# main.net
KiCad netlist of a schematic drawn in Altium Designer
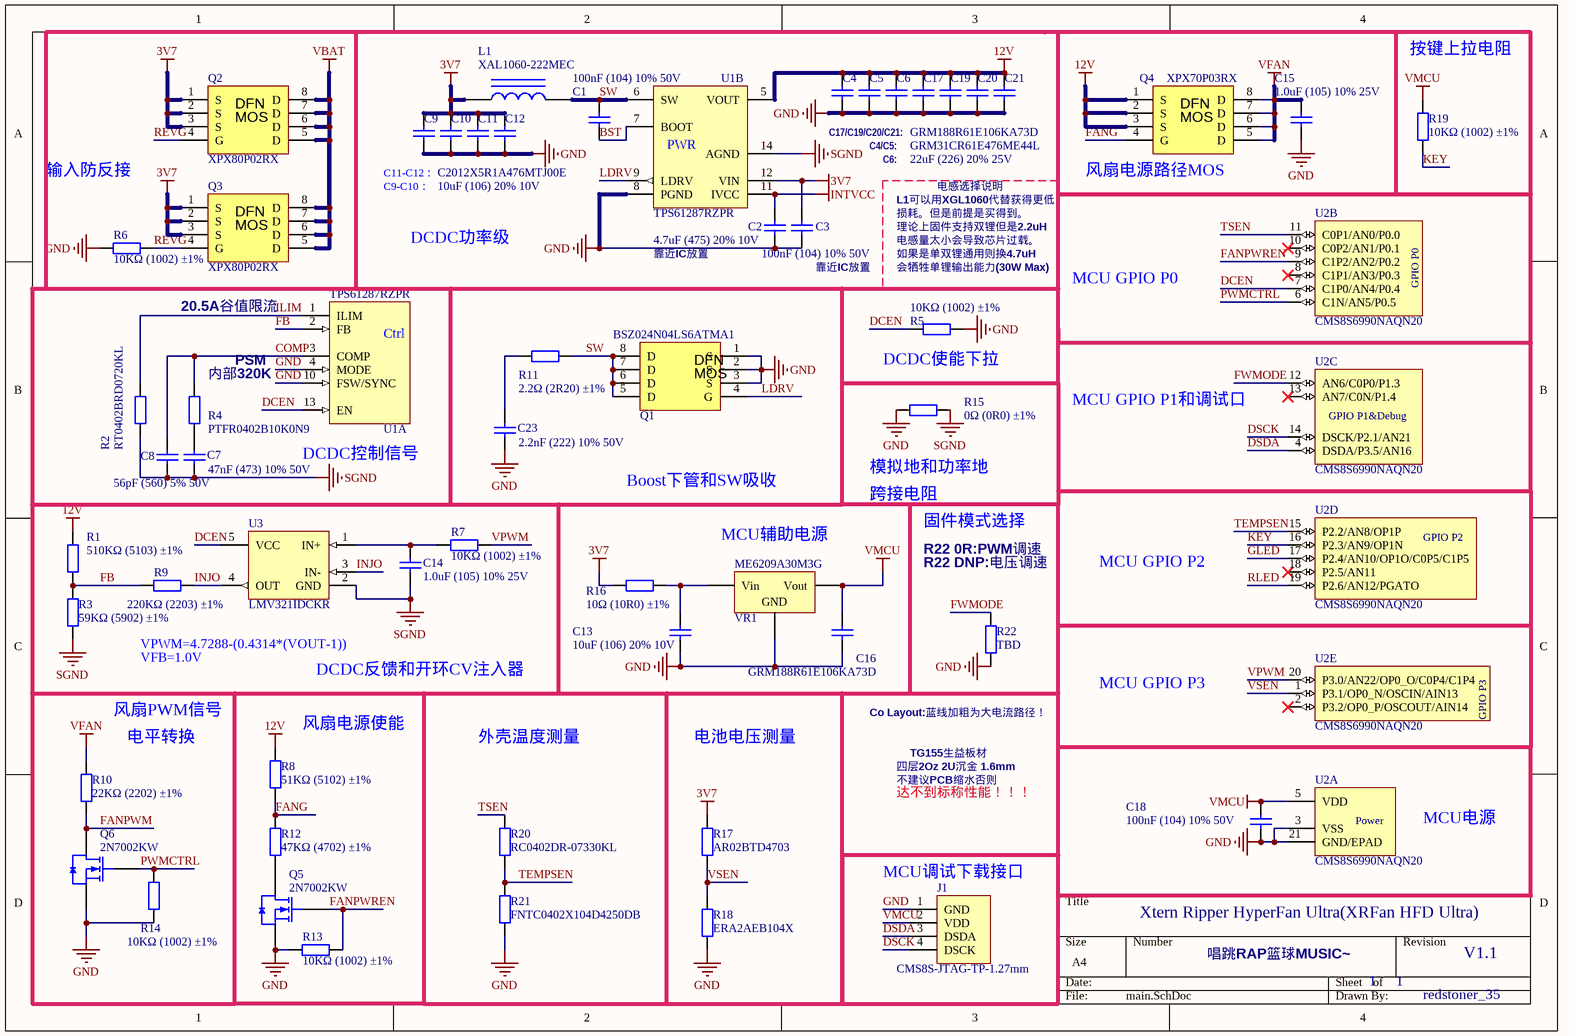
[diagram p0: main.SchDoc]

(export (version "E")
  (design (tool "Eeschema 10.0.6"))
  (components
    (comp (ref "C1")
      (value "100nF (104) 10% 50V")
      (footprint "0402_C")
      (description "贴片电容")
      (libsource (lib "Miscellaneous Devices LC") (part "0402 100nF (104) 10% 16V"))
    )
    (comp (ref "C2")
      (value "4.7uF (475) 20% 10V")
      (footprint "0402_C")
      (description "贴片电容")
      (libsource (lib "Miscellaneous Devices LC") (part "0402 4.7uF (475) 20% 10V"))
    )
    (comp (ref "C3")
      (value "100nF (104) 10% 50V")
      (footprint "0402_C")
      (description "贴片电容")
      (libsource (lib "Miscellaneous Devices LC") (part "0402 100nF (104) 10% 16V"))
    )
    (comp (ref "C4")
      (value "GRM31CR61E476ME44L")
      (footprint "1206C")
      (description "1206尺寸村田MLCC 25V 47uF X5R ±20%")
      (fields (field (name "PUBLISHER") "Altium Limited"))
      (libsource (lib "山猫的集成库20190318") (part "Cap"))
    )
    (comp (ref "C5")
      (value "GRM31CR61E476ME44L")
      (footprint "1206C")
      (description "1206尺寸村田MLCC 25V 47uF X5R ±20%")
      (fields (field (name "PUBLISHER") "Altium Limited"))
      (libsource (lib "山猫的集成库20190318") (part "Cap"))
    )
    (comp (ref "C6")
      (value "22uF (226) 20% 25V")
      (footprint "0805_C")
      (description "贴片电容")
      (libsource (lib "Miscellaneous Devices LC") (part "0805 22uF (226) 20% 25V"))
    )
    (comp (ref "C7")
      (value "47nF (473) 10% 50V")
      (footprint "0402_C")
      (description "贴片电容")
      (libsource (lib "Miscellaneous Devices LC") (part "0402 100nF (104) 10% 16V"))
    )
    (comp (ref "C8")
      (value "56pF (560) 5% 50V")
      (footprint "0402_C")
      (description "贴片电容")
      (libsource (lib "Miscellaneous Devices LC") (part "0402 56pF (560) 5% 50V"))
    )
    (comp (ref "C9")
      (value "10uF (106) 20% 10V")
      (footprint "0402_C")
      (description "贴片电容")
      (libsource (lib "Miscellaneous Devices LC") (part "0402 10uF (106) 20% 6.3V"))
    )
    (comp (ref "C10")
      (value "10uF (106) 20% 10V")
      (footprint "0402_C")
      (description "贴片电容")
      (libsource (lib "Miscellaneous Devices LC") (part "0402 10uF (106) 20% 6.3V"))
    )
    (comp (ref "C11")
      (value "C2012X5R1A476MTJ00E")
      (footprint "0805_C")
      (description "贴片MLCC电容，X5R 47uF ±20% 10V")
      (libsource (lib "Miscellaneous Devices LC") (part "0805 22uF (226) 20% 25V"))
    )
    (comp (ref "C12")
      (value "C2012X5R1A476MTJ00E")
      (footprint "0805_C")
      (description "贴片MLCC电容，X5R 47uF ±20% 10V")
      (libsource (lib "Miscellaneous Devices LC") (part "0805 22uF (226) 20% 25V"))
    )
    (comp (ref "C13")
      (value "10uF (106) 20% 10V")
      (footprint "0402_C")
      (description "贴片电容")
      (libsource (lib "Miscellaneous Devices LC") (part "0402 10uF (106) 20% 6.3V"))
    )
    (comp (ref "C14")
      (value "1.0uF (105) 10% 25V")
      (footprint "0402_C")
      (description "贴片电容")
      (libsource (lib "Miscellaneous Devices LC") (part "0402 1.0uF (105) 10% 25V"))
    )
    (comp (ref "C15")
      (value "1.0uF (105) 10% 25V")
      (footprint "0402_C")
      (description "贴片电容")
      (libsource (lib "Miscellaneous Devices LC") (part "0402 1.0uF (105) 10% 25V"))
    )
    (comp (ref "C16")
      (value "GRM188R61E106KA73D")
      (footprint "0603_C")
      (description "村田贴片MLCC电容 25V 10uF±20% X5R 0603封装")
      (libsource (lib "Miscellaneous Devices LC") (part "0603 10uF (106) 10% 10V"))
    )
    (comp (ref "C17")
      (value "GRM188R61E106KA73D")
      (footprint "0603_C")
      (description "村田贴片MLCC电容 25V 10uF±20% X5R 0603封装")
      (libsource (lib "Miscellaneous Devices LC") (part "0603 10uF (106) 10% 10V"))
    )
    (comp (ref "C18")
      (value "100nF (104) 10% 50V")
      (footprint "0402_C")
      (description "贴片电容")
      (libsource (lib "Miscellaneous Devices LC") (part "0402 100nF (104) 10% 16V"))
    )
    (comp (ref "C19")
      (value "GRM188R61E106KA73D")
      (footprint "0603_C")
      (description "村田贴片MLCC电容 25V 10uF±20% X5R 0603封装")
      (libsource (lib "Miscellaneous Devices LC") (part "0603 10uF (106) 10% 10V"))
    )
    (comp (ref "C20")
      (value "GRM188R61E106KA73D")
      (footprint "0603_C")
      (description "村田贴片MLCC电容 25V 10uF±20% X5R 0603封装")
      (libsource (lib "Miscellaneous Devices LC") (part "0603 10uF (106) 10% 10V"))
    )
    (comp (ref "C21")
      (value "GRM188R61E106KA73D")
      (footprint "0603_C")
      (description "村田贴片MLCC电容 25V 10uF±20% X5R 0603封装")
      (libsource (lib "Miscellaneous Devices LC") (part "0603 10uF (106) 10% 10V"))
    )
    (comp (ref "C23")
      (value "2.2nF (222) 10% 50V")
      (footprint "0402_C")
      (description "贴片电容")
      (libsource (lib "Miscellaneous Devices LC") (part "0402 2.2nF (222) 10% 50V"))
    )
    (comp (ref "J1")
      (value "CMS8S-JTAG-TP-1.27mm")
      (footprint "CMS8S-JTAG-TP-2x2-P1.27")
      (description "面向CMS8S6990NA单片机的调试贴片触点，并不是元器件实物")
      (libsource (lib "custom") (part "CMS8S-JTAG-TP-1.27mm"))
    )
    (comp (ref "L1")
      (value "XAL1060-222MEC")
      (footprint "XAL1060-472ME-Lifted")
      (description "线艺一体成型模压电感，9.8mΩ DCR 25A饱和电流 4.7uH±20%电感量 10*11*6mm尺寸")
      (fields (field (name "PUBLISHER") "Altium Limited"))
      (libsource (lib "Miscellaneous Devices") (part "Inductor Iron"))
    )
    (comp (ref "Q1")
      (value "BSZ024N04LS6ATMA1")
      (footprint "DFN-8_L3.0-W3.0-P0.65-BL")
      (description "英飞凌OptiMOS 6 40V N沟道功率MOS 2.8mΩ@4.5V S3O8封装")
      (libsource (lib "") (part "SON/DFN5x6 MOS_1"))
    )
    (comp (ref "Q2")
      (value "XPX80P02RX")
      (footprint "DFN-8_L3.0-W3.0-P0.65-BL")
      (description "PDFN3x3 30V 50A N沟道MOSFET")
      (libsource (lib "custom") (part "SON/DFN5x6 MOS"))
    )
    (comp (ref "Q3")
      (value "XPX80P02RX")
      (footprint "DFN-8_L3.0-W3.0-P0.65-BL")
      (description "PDFN3x3 30V 50A N沟道MOSFET")
      (libsource (lib "custom") (part "SON/DFN5x6 MOS"))
    )
    (comp (ref "Q4")
      (value "XPX70P03RX")
      (footprint "DFN-8_L3.0-W3.0-P0.65-BL")
      (description "-30V -70A 6.5mR P沟道增强型MOSFET")
      (libsource (lib "custom") (part "SON/DFN5x6 MOS"))
    )
    (comp (ref "Q5")
      (value "2N7002KW")
      (footprint "SC70-3")
      (description "单N沟道MOSFET(场效应管)")
      (libsource (lib "Miscellaneous Devices LC") (part "2N7002 7002"))
    )
    (comp (ref "Q6")
      (value "2N7002KW")
      (footprint "SC70-3")
      (description "单N沟道MOSFET(场效应管)")
      (libsource (lib "Miscellaneous Devices LC") (part "2N7002 7002"))
    )
    (comp (ref "R1")
      (value "510KΩ (5103) ±1%")
      (footprint "0402_R")
      (description "贴片电阻")
      (libsource (lib "Miscellaneous Devices LC") (part "0402 510KΩ (5103) 1%"))
    )
    (comp (ref "R2")
      (value "RT0402BRD0720KL")
      (footprint "0402_R")
      (description "0402贴片薄膜高精密电阻 20KΩ ±0.1% 62.5mW 25PPM")
      (libsource (lib "Miscellaneous Devices LC") (part "0402 20KΩ (2002) 1%"))
    )
    (comp (ref "R3")
      (value "59KΩ (5902) ±1%")
      (footprint "0402_R")
      (description "贴片电阻")
      (libsource (lib "Miscellaneous Devices LC") (part "0402 510KΩ (5103) 1%"))
    )
    (comp (ref "R4")
      (value "PTFR0402B10K0N9")
      (footprint "0402_R")
      (description "0402贴片薄膜高精密电阻 10KΩ ±0.1% 62.5mW 25PPM")
      (libsource (lib "Miscellaneous Devices LC") (part "0402 12KΩ (1202) 1%"))
    )
    (comp (ref "R5")
      (value "10KΩ (1002) ±1%")
      (footprint "0402_R")
      (description "贴片电阻")
      (libsource (lib "Miscellaneous Devices LC") (part "0402 10KΩ (1002) 1%"))
    )
    (comp (ref "R6")
      (value "10KΩ (1002) ±1%")
      (footprint "0402_R")
      (description "贴片电阻")
      (libsource (lib "") (part "0402 10KΩ (1002) 1%_2"))
    )
    (comp (ref "R7")
      (value "10KΩ (1002) ±1%")
      (footprint "0402_R")
      (description "贴片电阻")
      (libsource (lib "") (part "0402 10KΩ (1002) 1%_2"))
    )
    (comp (ref "R8")
      (value "51KΩ (5102) ±1%")
      (footprint "0402_R")
      (description "贴片电阻")
      (libsource (lib "Miscellaneous Devices LC") (part "0402 47KΩ (4702) 1%"))
    )
    (comp (ref "R9")
      (value "220KΩ (2203) ±1%")
      (footprint "0402_R")
      (description "贴片电阻")
      (libsource (lib "Miscellaneous Devices LC") (part "0402 100KΩ (1003) 1%"))
    )
    (comp (ref "R10")
      (value "22KΩ (2202) ±1%")
      (footprint "0402_R")
      (description "贴片电阻")
      (libsource (lib "Miscellaneous Devices LC") (part "0402 22KΩ (2202) 1%"))
    )
    (comp (ref "R11")
      (value "2.2Ω (2R20) ±1%")
      (footprint "0603_R")
      (description "贴片电阻")
      (libsource (lib "Miscellaneous Devices LC") (part "0603 2.2Ω (2R20) 1%"))
    )
    (comp (ref "R12")
      (value "47KΩ (4702) ±1%")
      (footprint "0402_R")
      (description "贴片电阻")
      (libsource (lib "Miscellaneous Devices LC") (part "0402 51KΩ (5102) 1%"))
    )
    (comp (ref "R13")
      (value "10KΩ (1002) ±1%")
      (footprint "0402_R")
      (description "贴片电阻")
      (libsource (lib "Miscellaneous Devices LC") (part "0402 10KΩ (1002) 1%"))
    )
    (comp (ref "R14")
      (value "10KΩ (1002) ±1%")
      (footprint "0402_R")
      (description "贴片电阻")
      (libsource (lib "") (part "0402 10KΩ (1002) 1%_1"))
    )
    (comp (ref "R15")
      (value "0Ω (0R0) ±1%")
      (footprint "0402_R")
      (description "贴片电阻")
      (libsource (lib "Miscellaneous Devices LC") (part "0402 0Ω (0R0) 1%"))
    )
    (comp (ref "R16")
      (value "10Ω (10R0) ±1%")
      (footprint "0402_R")
      (description "贴片电阻")
      (libsource (lib "Miscellaneous Devices LC") (part "0402 10Ω (10R0) 1%"))
    )
    (comp (ref "R17")
      (value "AR02BTD4703")
      (footprint "0402_R")
      (description "0402 贴片薄膜高精密低温飘电阻 470KΩ±0.1% 25PPM")
      (libsource (lib "Miscellaneous Devices LC") (part "0402 470KΩ (4703) 1%"))
    )
    (comp (ref "R18")
      (value "ERA2AEB104X")
      (footprint "0402_R")
      (description "松下 0402精密低温飘贴片电阻 100KΩ±0.1% 62.5mW")
      (libsource (lib "") (part "0402 100KΩ (1003) 1%_1"))
    )
    (comp (ref "R19")
      (value "10KΩ (1002) ±1%")
      (footprint "0402_R")
      (description "贴片电阻")
      (libsource (lib "") (part "0402 10KΩ (1002) 1%_1"))
    )
    (comp (ref "R20")
      (value "RC0402DR-07330KL")
      (footprint "0402_R")
      (description "0402厚膜较高精度贴片电阻 330KΩ±0.5% 62.5mW")
      (libsource (lib "Miscellaneous Devices LC") (part "0402 470KΩ (4703) 1%"))
    )
    (comp (ref "R21")
      (value "FNTC0402X104D4250DB")
      (footprint "0402_R")
      (description "0402尺寸贴片式NTC热敏电阻 B25-85℃=4310±0.5% R25=100KΩ±0.5%")
      (libsource (lib "Miscellaneous Devices LC") (part "0402 200KΩ (2003) 1%"))
    )
    (comp (ref "R22")
      (value "TBD")
      (footprint "0402_R")
      (description "贴片电阻")
      (libsource (lib "") (part "0402 0Ω (0R0) 1%_1"))
    )
    (comp (ref "U1")
      (value "TPS61287RZPR")
      (footprint "RZP0014A-TPS61287")
      (description "Synchronous Boost Converter with Stackable Multi-Phase Function")
      (libsource (lib "custom") (part "TPS61287"))
    )
    (comp (ref "U2")
      (value "CMS8S6990NAQN20")
      (footprint "QFN40P300X300X800_HS-21N")
      (description "增强型闪存1T 8051单片机，16KB Flash 256+1K XRAM")
      (libsource (lib "custom") (part "CM8S6990NA-QFN20"))
    )
    (comp (ref "U3")
      (value "LMV321IDCKR")
      (footprint "SC70-5")
      (description "CMOS超小型运算放大器，SC70-5")
      (libsource (lib "custom") (part "LMV321IDCKR"))
    )
    (comp (ref "VR1")
      (value "ME6209A30M3G")
      (footprint "SOT-23-3L")
      (description "低压差线性稳压(LDO)")
      (libsource (lib "Miscellaneous Devices LC") (part "SOT-23 XC6206P332MR"))
    )
  )
  (nets
    (net (code "1") (name "/BST") (class "Default")
      (node (ref "C1") (pin "1") (pinfunction "1_1") (pintype "passive"))
      (node (ref "U1") (pin "7") (pinfunction "BOOT_7") (pintype "power_in"))
    )
    (net (code "2") (name "/COMP") (class "Default")
      (node (ref "C8") (pin "2") (pinfunction "2_2") (pintype "passive"))
      (node (ref "R4") (pin "2") (pinfunction "2_2") (pintype "passive"))
      (node (ref "U1") (pin "3") (pinfunction "COMP_3") (pintype "passive"))
    )
    (net (code "3") (name "/DCEN") (class "Default")
      (node (ref "R5") (pin "2") (pinfunction "2_2") (pintype "passive"))
      (node (ref "U1") (pin "13") (pinfunction "EN_13") (pintype "input"))
      (node (ref "U2") (pin "7") (pinfunction "C1P0/AN4/P0.4_7") (pintype "bidirectional"))
      (node (ref "U3") (pin "5") (pinfunction "VCC_5") (pintype "power_in"))
    )
    (net (code "4") (name "/DSCK") (class "Default")
      (node (ref "J1") (pin "4") (pinfunction "DSCK_4") (pintype "passive"))
      (node (ref "U2") (pin "14") (pinfunction "DSCK/P2.1/AN21_14") (pintype "bidirectional"))
    )
    (net (code "5") (name "/DSDA") (class "Default")
      (node (ref "J1") (pin "3") (pinfunction "DSDA_3") (pintype "passive"))
      (node (ref "U2") (pin "4") (pinfunction "DSDA/P3.5/AN16_4") (pintype "bidirectional"))
    )
    (net (code "6") (name "/FANG") (class "Default")
      (node (ref "Q4") (pin "4") (pinfunction "G_4") (pintype "passive"))
      (node (ref "R12") (pin "2") (pinfunction "2_2") (pintype "passive"))
      (node (ref "R8") (pin "1") (pinfunction "1_1") (pintype "passive"))
    )
    (net (code "7") (name "/FANPWM") (class "Default")
      (node (ref "Q6") (pin "3") (pinfunction "D_3") (pintype "passive"))
      (node (ref "R10") (pin "1") (pinfunction "1_1") (pintype "passive"))
    )
    (net (code "8") (name "/FANPWREN") (class "Default")
      (node (ref "Q5") (pin "1") (pinfunction "G_1") (pintype "passive"))
      (node (ref "R13") (pin "1") (pinfunction "1_1") (pintype "passive"))
      (node (ref "U2") (pin "9") (pinfunction "C1P2/AN2/P0.2_9") (pintype "bidirectional"))
    )
    (net (code "9") (name "/FB") (class "Default")
      (node (ref "R1") (pin "1") (pinfunction "1_1") (pintype "passive"))
      (node (ref "R3") (pin "2") (pinfunction "2_2") (pintype "passive"))
      (node (ref "R9") (pin "1") (pinfunction "1_1") (pintype "passive"))
      (node (ref "U1") (pin "2") (pinfunction "FB_2") (pintype "input"))
    )
    (net (code "10") (name "/FWMODE") (class "Default")
      (node (ref "R22") (pin "1") (pinfunction "1_1") (pintype "passive"))
      (node (ref "U2") (pin "12") (pinfunction "AN6/C0P0/P1.3_12") (pintype "bidirectional"))
    )
    (net (code "11") (name "/GLED") (class "Default")
      (node (ref "U2") (pin "17") (pinfunction "P2.4/AN10/OP1O/C0P5/C1P5_17") (pintype "bidirectional"))
    )
    (net (code "12") (name "/ILIM") (class "Default")
      (node (ref "R2") (pin "1") (pinfunction "1_1") (pintype "passive"))
      (node (ref "U1") (pin "1") (pinfunction "ILIM_1") (pintype "passive"))
    )
    (net (code "13") (name "/INJO") (class "Default")
      (node (ref "R9") (pin "2") (pinfunction "2_2") (pintype "passive"))
      (node (ref "U3") (pin "3") (pinfunction "IN-_3") (pintype "input"))
      (node (ref "U3") (pin "4") (pinfunction "OUT_4") (pintype "output"))
    )
    (net (code "14") (name "/KEY") (class "Default")
      (node (ref "R19") (pin "1") (pinfunction "1_1") (pintype "passive"))
      (node (ref "U2") (pin "16") (pinfunction "P2.3/AN9/OP1N_16") (pintype "bidirectional"))
    )
    (net (code "15") (name "/LDRV") (class "Default")
      (node (ref "Q1") (pin "4") (pinfunction "G_4") (pintype "passive"))
      (node (ref "U1") (pin "9") (pinfunction "LDRV_9") (pintype "output"))
    )
    (net (code "16") (name "/PWMCTRL") (class "Default")
      (node (ref "Q6") (pin "1") (pinfunction "G_1") (pintype "passive"))
      (node (ref "R14") (pin "2") (pinfunction "2_2") (pintype "passive"))
      (node (ref "U2") (pin "6") (pinfunction "C1N/AN5/P0.5_6") (pintype "bidirectional"))
    )
    (net (code "17") (name "/REVG") (class "Default")
      (node (ref "Q2") (pin "4") (pinfunction "G_4") (pintype "passive"))
      (node (ref "Q3") (pin "4") (pinfunction "G_4") (pintype "passive"))
      (node (ref "R6") (pin "2") (pinfunction "2_2") (pintype "passive"))
    )
    (net (code "18") (name "/RLED") (class "Default")
      (node (ref "U2") (pin "19") (pinfunction "P2.6/AN12/PGATO_19") (pintype "bidirectional"))
    )
    (net (code "19") (name "/SW") (class "Default")
      (node (ref "C1") (pin "2") (pinfunction "2_2") (pintype "passive"))
      (node (ref "L1") (pin "2") (pinfunction "2_2") (pintype "passive"))
      (node (ref "Q1") (pin "5") (pinfunction "D_5") (pintype "passive"))
      (node (ref "Q1") (pin "6") (pinfunction "D_6") (pintype "passive"))
      (node (ref "Q1") (pin "7") (pinfunction "D_7") (pintype "passive"))
      (node (ref "Q1") (pin "8") (pinfunction "D_8") (pintype "passive"))
      (node (ref "R11") (pin "2") (pinfunction "2_2") (pintype "passive"))
      (node (ref "U1") (pin "6") (pinfunction "SW_6") (pintype "power_in"))
    )
    (net (code "20") (name "/TEMPSEN") (class "Default")
      (node (ref "R20") (pin "1") (pinfunction "1_1") (pintype "passive"))
      (node (ref "R21") (pin "2") (pinfunction "2_2") (pintype "passive"))
      (node (ref "U2") (pin "15") (pinfunction "P2.2/AN8/OP1P_15") (pintype "bidirectional"))
    )
    (net (code "21") (name "/TSEN") (class "Default")
      (node (ref "R20") (pin "2") (pinfunction "2_2") (pintype "passive"))
      (node (ref "U2") (pin "11") (pinfunction "C0P1/AN0/P0.0_11") (pintype "bidirectional"))
    )
    (net (code "22") (name "/VPWM") (class "Default")
      (node (ref "R7") (pin "2") (pinfunction "2_2") (pintype "passive"))
      (node (ref "U2") (pin "20") (pinfunction "P3.0/AN22/OP0_O/C0P4/C1P4_20") (pintype "bidirectional"))
    )
    (net (code "23") (name "/VSEN") (class "Default")
      (node (ref "R17") (pin "1") (pinfunction "1_1") (pintype "passive"))
      (node (ref "R18") (pin "2") (pinfunction "2_2") (pintype "passive"))
      (node (ref "U2") (pin "1") (pinfunction "P3.1/OP0_N/OSCIN/AIN13_1") (pintype "bidirectional"))
    )
    (net (code "24") (name "3V7") (class "Default")
      (node (ref "C10") (pin "2") (pinfunction "2_2") (pintype "passive"))
      (node (ref "C11") (pin "2") (pinfunction "2_2") (pintype "passive"))
      (node (ref "C12") (pin "2") (pinfunction "2_2") (pintype "passive"))
      (node (ref "C3") (pin "2") (pinfunction "2_2") (pintype "passive"))
      (node (ref "C9") (pin "2") (pinfunction "2_2") (pintype "passive"))
      (node (ref "L1") (pin "1") (pinfunction "1_1") (pintype "passive"))
      (node (ref "Q2") (pin "1") (pinfunction "S_1") (pintype "passive"))
      (node (ref "Q2") (pin "2") (pinfunction "S_2") (pintype "passive"))
      (node (ref "Q2") (pin "3") (pinfunction "S_3") (pintype "passive"))
      (node (ref "Q3") (pin "1") (pinfunction "S_1") (pintype "passive"))
      (node (ref "Q3") (pin "2") (pinfunction "S_2") (pintype "passive"))
      (node (ref "Q3") (pin "3") (pinfunction "S_3") (pintype "passive"))
      (node (ref "R16") (pin "1") (pinfunction "1_1") (pintype "passive"))
      (node (ref "R17") (pin "2") (pinfunction "2_2") (pintype "passive"))
      (node (ref "U1") (pin "12") (pinfunction "VIN_12") (pintype "power_in"))
    )
    (net (code "25") (name "12V") (class "Default")
      (node (ref "C17") (pin "2") (pinfunction "2_2") (pintype "passive"))
      (node (ref "C19") (pin "2") (pinfunction "2_2") (pintype "passive"))
      (node (ref "C20") (pin "2") (pinfunction "2_2") (pintype "passive"))
      (node (ref "C21") (pin "2") (pinfunction "2_2") (pintype "passive"))
      (node (ref "C4") (pin "2") (pinfunction "2_2") (pintype "passive"))
      (node (ref "C5") (pin "2") (pinfunction "2_2") (pintype "passive"))
      (node (ref "C6") (pin "2") (pinfunction "2_2") (pintype "passive"))
      (node (ref "Q4") (pin "1") (pinfunction "S_1") (pintype "passive"))
      (node (ref "Q4") (pin "2") (pinfunction "S_2") (pintype "passive"))
      (node (ref "Q4") (pin "3") (pinfunction "S_3") (pintype "passive"))
      (node (ref "R1") (pin "2") (pinfunction "2_2") (pintype "passive"))
      (node (ref "R8") (pin "2") (pinfunction "2_2") (pintype "passive"))
      (node (ref "U1") (pin "5") (pinfunction "VOUT_5") (pintype "power_in"))
    )
    (net (code "26") (name "GND") (class "Default")
      (node (ref "C10") (pin "1") (pinfunction "1_1") (pintype "passive"))
      (node (ref "C11") (pin "1") (pinfunction "1_1") (pintype "passive"))
      (node (ref "C12") (pin "1") (pinfunction "1_1") (pintype "passive"))
      (node (ref "C13") (pin "1") (pinfunction "1_1") (pintype "passive"))
      (node (ref "C15") (pin "1") (pinfunction "1_1") (pintype "passive"))
      (node (ref "C16") (pin "1") (pinfunction "1_1") (pintype "passive"))
      (node (ref "C17") (pin "1") (pinfunction "1_1") (pintype "passive"))
      (node (ref "C18") (pin "1") (pinfunction "1_1") (pintype "passive"))
      (node (ref "C19") (pin "1") (pinfunction "1_1") (pintype "passive"))
      (node (ref "C2") (pin "1") (pinfunction "1_1") (pintype "passive"))
      (node (ref "C20") (pin "1") (pinfunction "1_1") (pintype "passive"))
      (node (ref "C21") (pin "1") (pinfunction "1_1") (pintype "passive"))
      (node (ref "C23") (pin "1") (pinfunction "1_1") (pintype "passive"))
      (node (ref "C3") (pin "1") (pinfunction "1_1") (pintype "passive"))
      (node (ref "C4") (pin "1") (pinfunction "1_1") (pintype "passive"))
      (node (ref "C5") (pin "1") (pinfunction "1_1") (pintype "passive"))
      (node (ref "C6") (pin "1") (pinfunction "1_1") (pintype "passive"))
      (node (ref "C9") (pin "1") (pinfunction "1_1") (pintype "passive"))
      (node (ref "J1") (pin "1") (pinfunction "GND_1") (pintype "passive"))
      (node (ref "Q1") (pin "1") (pinfunction "S_1") (pintype "passive"))
      (node (ref "Q1") (pin "2") (pinfunction "S_2") (pintype "passive"))
      (node (ref "Q1") (pin "3") (pinfunction "S_3") (pintype "passive"))
      (node (ref "Q5") (pin "2") (pinfunction "S_2") (pintype "passive"))
      (node (ref "Q6") (pin "2") (pinfunction "S_2") (pintype "passive"))
      (node (ref "R13") (pin "2") (pinfunction "2_2") (pintype "passive"))
      (node (ref "R14") (pin "1") (pinfunction "1_1") (pintype "passive"))
      (node (ref "R15") (pin "1") (pinfunction "1_1") (pintype "passive"))
      (node (ref "R18") (pin "1") (pinfunction "1_1") (pintype "passive"))
      (node (ref "R21") (pin "1") (pinfunction "1_1") (pintype "passive"))
      (node (ref "R22") (pin "2") (pinfunction "2_2") (pintype "passive"))
      (node (ref "R5") (pin "1") (pinfunction "1_1") (pintype "passive"))
      (node (ref "R6") (pin "1") (pinfunction "1_1") (pintype "passive"))
      (node (ref "U1") (pin "10") (pinfunction "FSW/SYNC_10") (pintype "input"))
      (node (ref "U1") (pin "4") (pinfunction "MODE_4") (pintype "input"))
      (node (ref "U1") (pin "8") (pinfunction "PGND_8") (pintype "power_in"))
      (node (ref "U2") (pin "21") (pinfunction "GND/EPAD_21") (pintype "power_in"))
      (node (ref "U2") (pin "3") (pinfunction "VSS_3") (pintype "power_in"))
      (node (ref "VR1") (pin "1") (pinfunction "GND_1") (pintype "passive"))
    )
    (net (code "27") (name "INTVCC") (class "Default")
      (node (ref "C2") (pin "2") (pinfunction "2_2") (pintype "passive"))
      (node (ref "U1") (pin "11") (pinfunction "IVCC_11") (pintype "power_in"))
    )
    (net (code "28") (name "Net-(C7-Pad2)") (class "Default")
      (node (ref "C7") (pin "2") (pinfunction "2_2") (pintype "passive"))
      (node (ref "R4") (pin "1") (pinfunction "1_1") (pintype "passive"))
    )
    (net (code "29") (name "Net-(C23-Pad2)") (class "Default")
      (node (ref "C23") (pin "2") (pinfunction "2_2") (pintype "passive"))
      (node (ref "R11") (pin "1") (pinfunction "1_1") (pintype "passive"))
    )
    (net (code "30") (name "Net-(Q5-D)") (class "Default")
      (node (ref "Q5") (pin "3") (pinfunction "D_3") (pintype "passive"))
      (node (ref "R12") (pin "1") (pinfunction "1_1") (pintype "passive"))
    )
    (net (code "31") (name "Net-(U3-IN+)") (class "Default")
      (node (ref "C14") (pin "2") (pinfunction "2_2") (pintype "passive"))
      (node (ref "R7") (pin "1") (pinfunction "1_1") (pintype "passive"))
      (node (ref "U3") (pin "1") (pinfunction "IN+_1") (pintype "input"))
    )
    (net (code "32") (name "Net-(VR1-Vin)") (class "Default")
      (node (ref "C13") (pin "2") (pinfunction "2_2") (pintype "passive"))
      (node (ref "R16") (pin "2") (pinfunction "2_2") (pintype "passive"))
      (node (ref "VR1") (pin "3") (pinfunction "Vin_3") (pintype "passive"))
    )
    (net (code "33") (name "SGND") (class "Default")
      (node (ref "C14") (pin "1") (pinfunction "1_1") (pintype "passive"))
      (node (ref "C7") (pin "1") (pinfunction "1_1") (pintype "passive"))
      (node (ref "C8") (pin "1") (pinfunction "1_1") (pintype "passive"))
      (node (ref "R15") (pin "2") (pinfunction "2_2") (pintype "passive"))
      (node (ref "R2") (pin "2") (pinfunction "2_2") (pintype "passive"))
      (node (ref "R3") (pin "1") (pinfunction "1_1") (pintype "passive"))
      (node (ref "U1") (pin "14") (pinfunction "AGND_14") (pintype "power_in"))
      (node (ref "U3") (pin "2") (pinfunction "GND_2") (pintype "power_in"))
    )
    (net (code "34") (name "VBAT") (class "Default")
      (node (ref "Q2") (pin "5") (pinfunction "D_5") (pintype "passive"))
      (node (ref "Q2") (pin "6") (pinfunction "D_6") (pintype "passive"))
      (node (ref "Q2") (pin "7") (pinfunction "D_7") (pintype "passive"))
      (node (ref "Q2") (pin "8") (pinfunction "D_8") (pintype "passive"))
      (node (ref "Q3") (pin "5") (pinfunction "D_5") (pintype "passive"))
      (node (ref "Q3") (pin "6") (pinfunction "D_6") (pintype "passive"))
      (node (ref "Q3") (pin "7") (pinfunction "D_7") (pintype "passive"))
      (node (ref "Q3") (pin "8") (pinfunction "D_8") (pintype "passive"))
    )
    (net (code "35") (name "VFAN") (class "Default")
      (node (ref "C15") (pin "2") (pinfunction "2_2") (pintype "passive"))
      (node (ref "Q4") (pin "5") (pinfunction "D_5") (pintype "passive"))
      (node (ref "Q4") (pin "6") (pinfunction "D_6") (pintype "passive"))
      (node (ref "Q4") (pin "7") (pinfunction "D_7") (pintype "passive"))
      (node (ref "Q4") (pin "8") (pinfunction "D_8") (pintype "passive"))
      (node (ref "R10") (pin "2") (pinfunction "2_2") (pintype "passive"))
    )
    (net (code "36") (name "VMCU") (class "Default")
      (node (ref "C16") (pin "2") (pinfunction "2_2") (pintype "passive"))
      (node (ref "C18") (pin "2") (pinfunction "2_2") (pintype "passive"))
      (node (ref "J1") (pin "2") (pinfunction "VDD_2") (pintype "passive"))
      (node (ref "R19") (pin "2") (pinfunction "2_2") (pintype "passive"))
      (node (ref "U2") (pin "5") (pinfunction "VDD_5") (pintype "power_in"))
      (node (ref "VR1") (pin "2") (pinfunction "Vout_2") (pintype "passive"))
    )
    (net (code "37") (name "unconnected-(U2B-C0P2{slash}AN1{slash}P0.1-Pad10)") (class "Default")
      (node (ref "U2") (pin "10") (pinfunction "C0P2/AN1/P0.1_10") (pintype "bidirectional+no_connect"))
    )
    (net (code "38") (name "unconnected-(U2B-C1P1{slash}AN3{slash}P0.3-Pad8)") (class "Default")
      (node (ref "U2") (pin "8") (pinfunction "C1P1/AN3/P0.3_8") (pintype "bidirectional+no_connect"))
    )
    (net (code "39") (name "unconnected-(U2C-AN7{slash}C0N{slash}P1.4-Pad13)") (class "Default")
      (node (ref "U2") (pin "13") (pinfunction "AN7/C0N/P1.4_13") (pintype "bidirectional+no_connect"))
    )
    (net (code "40") (name "unconnected-(U2D-P2.5{slash}AN11-Pad18)") (class "Default")
      (node (ref "U2") (pin "18") (pinfunction "P2.5/AN11_18") (pintype "bidirectional+no_connect"))
    )
    (net (code "41") (name "unconnected-(U2E-P3.2{slash}OP0_P{slash}OSCOUT{slash}AIN14-Pad2)") (class "Default")
      (node (ref "U2") (pin "2") (pinfunction "P3.2/OP0_P/OSCOUT/AIN14_2") (pintype "bidirectional+no_connect"))
    )
  )
)
